# ArdZeroBTHIDStickBckUp.net
KiCad netlist of a schematic drawn in EAGLE
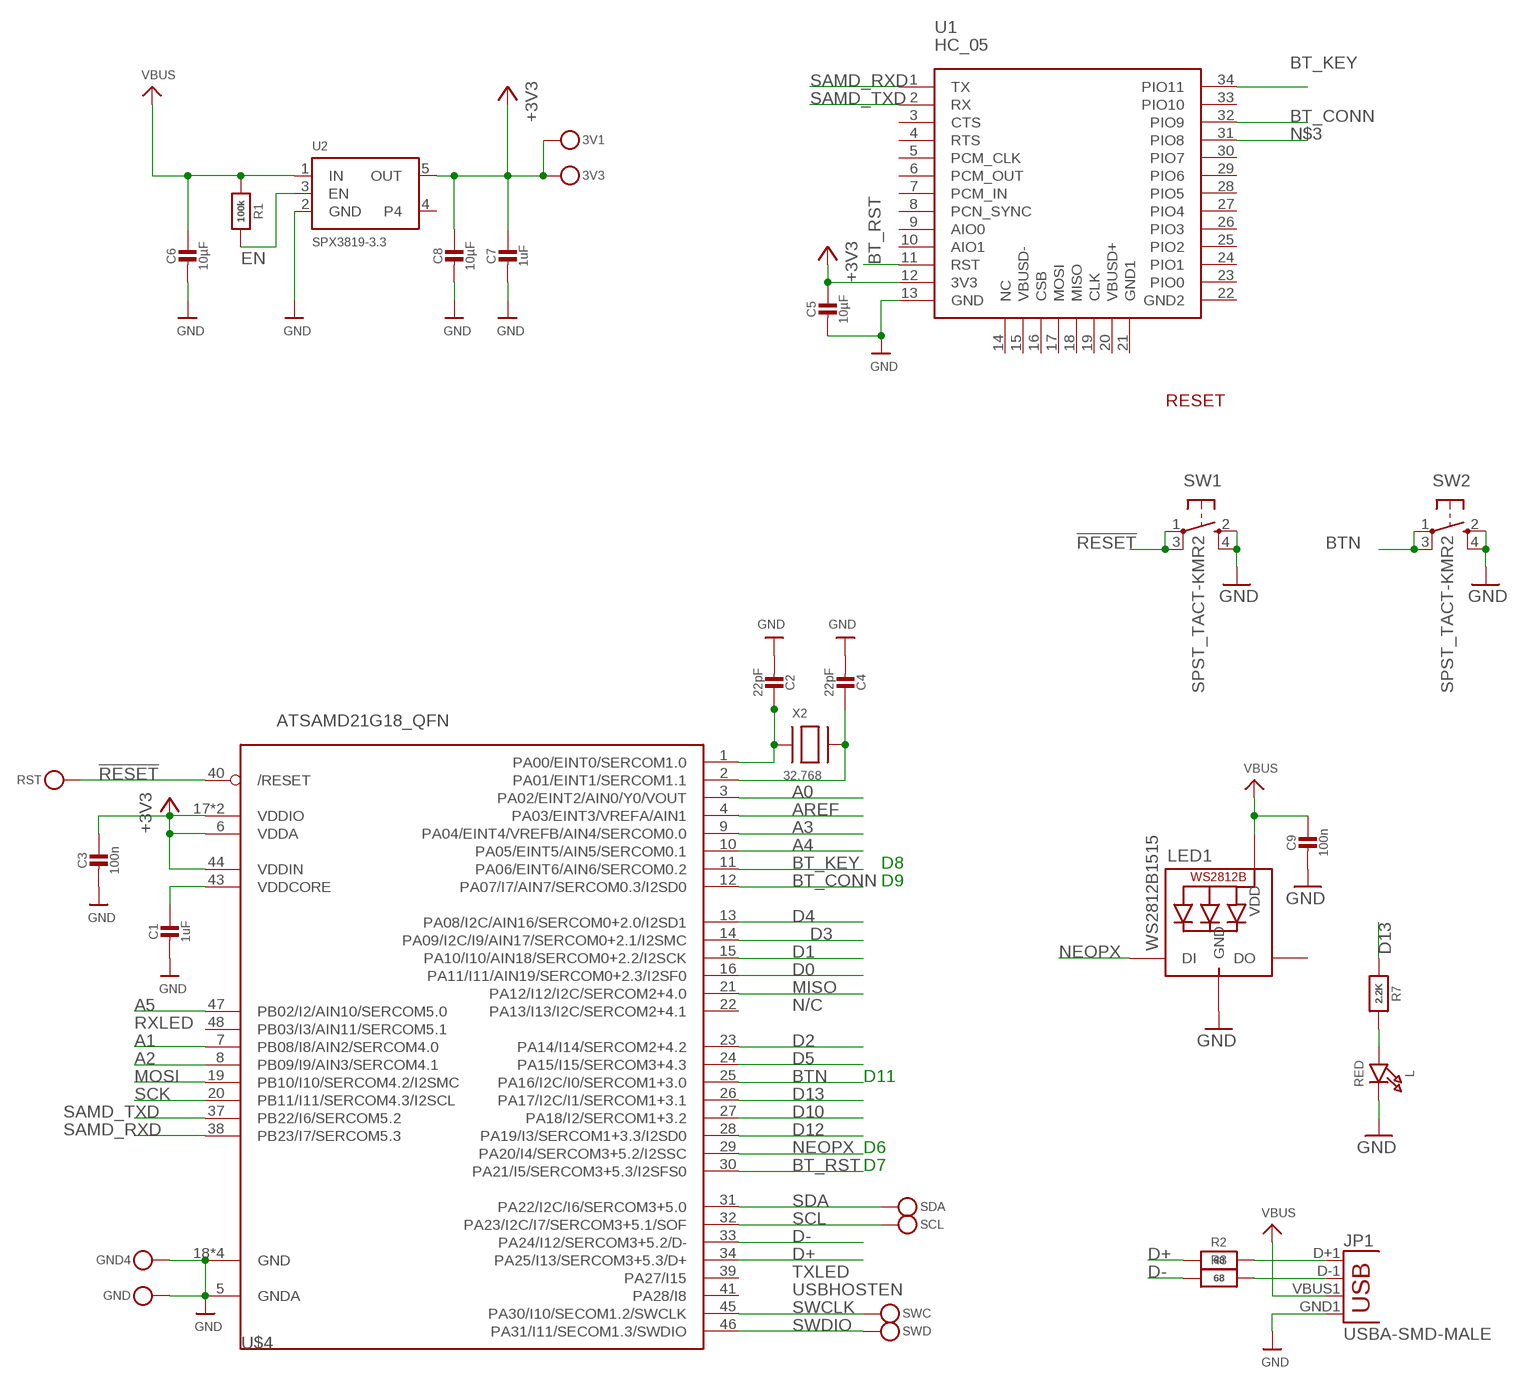
[diagram p0: schematic, sheet 1]

(export (version "E")
  (design (tool "Eeschema 10.0.6"))
  (components
    (comp (ref "3V1")
      (value "TESTPOINTROUND1.5MM")
      (footprint "eagle-import:TESTPOINT_ROUND_1.5MM")
      (libsource (lib "eagle-import") (part "TESTPOINTROUND1.5MM"))
    )
    (comp (ref "3V3")
      (value "TESTPOINTROUND1.5MM")
      (footprint "eagle-import:TESTPOINT_ROUND_1.5MM")
      (libsource (lib "eagle-import") (part "TESTPOINTROUND1.5MM"))
    )
    (comp (ref "C1")
      (value "1uF")
      (footprint "eagle-import:0603-NO")
      (libsource (lib "eagle-import") (part "CAP_CERAMIC0603_NO"))
    )
    (comp (ref "C2")
      (value "22pF")
      (footprint "eagle-import:0603-NO")
      (libsource (lib "eagle-import") (part "CAP_CERAMIC0603_NO"))
    )
    (comp (ref "C3")
      (value "100n")
      (footprint "eagle-import:0603-NO")
      (libsource (lib "eagle-import") (part "CAP_CERAMIC0603_NO"))
    )
    (comp (ref "C4")
      (value "22pF")
      (footprint "eagle-import:0603-NO")
      (libsource (lib "eagle-import") (part "CAP_CERAMIC0603_NO"))
    )
    (comp (ref "C5")
      (value "10µF")
      (footprint "eagle-import:0805-NO")
      (libsource (lib "eagle-import") (part "CAP_CERAMIC0805-NOOUTLINE"))
    )
    (comp (ref "C6")
      (value "10µF")
      (footprint "eagle-import:0805-NO")
      (libsource (lib "eagle-import") (part "CAP_CERAMIC0805-NOOUTLINE"))
    )
    (comp (ref "C7")
      (value "1uF")
      (footprint "eagle-import:0603-NO")
      (libsource (lib "eagle-import") (part "CAP_CERAMIC0603_NO"))
    )
    (comp (ref "C8")
      (value "10µF")
      (footprint "eagle-import:0805-NO")
      (libsource (lib "eagle-import") (part "CAP_CERAMIC0805-NOOUTLINE"))
    )
    (comp (ref "C9")
      (value "100n")
      (footprint "eagle-import:0603-NO")
      (libsource (lib "eagle-import") (part "CAP_CERAMIC0603_NO"))
    )
    (comp (ref "GND")
      (value "TESTPOINTROUND1.5MM")
      (footprint "eagle-import:TESTPOINT_ROUND_1.5MM")
      (libsource (lib "eagle-import") (part "TESTPOINTROUND1.5MM"))
    )
    (comp (ref "GND4")
      (value "TESTPOINTROUND1.5MM")
      (footprint "eagle-import:TESTPOINT_ROUND_1.5MM")
      (libsource (lib "eagle-import") (part "TESTPOINTROUND1.5MM"))
    )
    (comp (ref "JP1")
      (value "USBA-SMD-MALE")
      (footprint "eagle-import:USB-A-SMT-MALE")
      (libsource (lib "eagle-import") (part "USBA-SMD-MALE"))
    )
    (comp (ref "L")
      (value "RED")
      (footprint "eagle-import:CHIPLED_0805_NOOUTLINE")
      (libsource (lib "eagle-import") (part "LED0805_NOOUTLINE"))
    )
    (comp (ref "LED1")
      (value "WS2812B1515")
      (footprint "eagle-import:LED1515")
      (libsource (lib "eagle-import") (part "WS2812B1515"))
    )
    (comp (ref "R1")
      (value "100k")
      (footprint "eagle-import:0603-NO")
      (libsource (lib "eagle-import") (part "RESISTOR_0603_NOOUT"))
    )
    (comp (ref "R2")
      (value "68")
      (footprint "eagle-import:0603-NO")
      (libsource (lib "eagle-import") (part "RESISTOR_0603_NOOUT"))
    )
    (comp (ref "R3")
      (value "68")
      (footprint "eagle-import:0603-NO")
      (libsource (lib "eagle-import") (part "RESISTOR_0603_NOOUT"))
    )
    (comp (ref "R7")
      (value "2.2K")
      (footprint "eagle-import:0603-NO")
      (libsource (lib "eagle-import") (part "RESISTOR_0603_NOOUT"))
    )
    (comp (ref "RST")
      (value "TESTPOINTROUND1.5MM")
      (footprint "eagle-import:TESTPOINT_ROUND_1.5MM")
      (libsource (lib "eagle-import") (part "TESTPOINTROUND1.5MM"))
    )
    (comp (ref "SCL")
      (value "TESTPOINTROUND1.5MM")
      (footprint "eagle-import:TESTPOINT_ROUND_1.5MM")
      (libsource (lib "eagle-import") (part "TESTPOINTROUND1.5MM"))
    )
    (comp (ref "SDA")
      (value "TESTPOINTROUND1.5MM")
      (footprint "eagle-import:TESTPOINT_ROUND_1.5MM")
      (libsource (lib "eagle-import") (part "TESTPOINTROUND1.5MM"))
    )
    (comp (ref "SW1")
      (value "SPST_TACT-KMR2")
      (footprint "eagle-import:KMR2")
      (libsource (lib "eagle-import") (part "SPST_TACT-KMR2"))
    )
    (comp (ref "SW2")
      (value "SPST_TACT-KMR2")
      (footprint "eagle-import:KMR2")
      (libsource (lib "eagle-import") (part "SPST_TACT-KMR2"))
    )
    (comp (ref "SWC")
      (value "TESTPOINTROUND1.5MM")
      (footprint "eagle-import:TESTPOINT_ROUND_1.5MM")
      (libsource (lib "eagle-import") (part "TESTPOINTROUND1.5MM"))
    )
    (comp (ref "SWD")
      (value "TESTPOINTROUND1.5MM")
      (footprint "eagle-import:TESTPOINT_ROUND_1.5MM")
      (libsource (lib "eagle-import") (part "TESTPOINTROUND1.5MM"))
    )
    (comp (ref "U$4")
      (value "ATSAMD21G18_QFN")
      (footprint "eagle-import:TQFN48_7MM")
      (libsource (lib "eagle-import") (part "ATSAMD21J_QFN"))
    )
    (comp (ref "U1")
      (value "HC_05")
      (footprint "eagle-import:BLUETOOTH_SMD")
      (libsource (lib "eagle-import") (part "HC_05"))
    )
    (comp (ref "U2")
      (value "SPX3819-3.3")
      (footprint "eagle-import:SOT23-5")
      (libsource (lib "eagle-import") (part "VREG_SOT23-5"))
    )
    (comp (ref "X2")
      (value "32.768")
      (footprint "eagle-import:XTAL3215")
      (libsource (lib "eagle-import") (part "XTAL-3.2X1.5"))
    )
  )
  (nets
    (net (code "1") (name "+3V3") (class "Default")
      (node (ref "3V1") (pin "P$1") (pinfunction "P$1_P$1") (pintype "bidirectional"))
      (node (ref "3V3") (pin "P$1") (pinfunction "P$1_P$1") (pintype "bidirectional"))
      (node (ref "C3") (pin "1") (pinfunction "1_1") (pintype "passive"))
      (node (ref "C5") (pin "1") (pinfunction "1_1") (pintype "passive"))
      (node (ref "C7") (pin "1") (pinfunction "1_1") (pintype "passive"))
      (node (ref "C8") (pin "1") (pinfunction "1_1") (pintype "passive"))
      (node (ref "U$4") (pin "17") (pinfunction "VDDIO_17") (pintype "power_in"))
      (node (ref "U$4") (pin "36") (pinfunction "VDDIO_36") (pintype "power_in"))
      (node (ref "U$4") (pin "44") (pinfunction "VDDIN_44") (pintype "power_in"))
      (node (ref "U$4") (pin "6") (pinfunction "VDDA_6") (pintype "power_in"))
      (node (ref "U1") (pin "12") (pinfunction "3V3_12") (pintype "bidirectional"))
      (node (ref "U2") (pin "5") (pinfunction "OUT_5") (pintype "power_in"))
    )
    (net (code "2") (name "/A0") (class "Default")
      (node (ref "U$4") (pin "3") (pinfunction "PA02/EINT2/AIN0/Y0/VOUT_3") (pintype "bidirectional"))
    )
    (net (code "3") (name "/A1") (class "Default")
      (node (ref "U$4") (pin "7") (pinfunction "PB08/I8/AIN2/SERCOM4.0_7") (pintype "bidirectional"))
    )
    (net (code "4") (name "/A2") (class "Default")
      (node (ref "U$4") (pin "8") (pinfunction "PB09/I9/AIN3/SERCOM4.1_8") (pintype "bidirectional"))
    )
    (net (code "5") (name "/A3") (class "Default")
      (node (ref "U$4") (pin "9") (pinfunction "PA04/EINT4/VREFB/AIN4/SERCOM0.0_9") (pintype "bidirectional"))
    )
    (net (code "6") (name "/A4") (class "Default")
      (node (ref "U$4") (pin "10") (pinfunction "PA05/EINT5/AIN5/SERCOM0.1_10") (pintype "bidirectional"))
    )
    (net (code "7") (name "/A5") (class "Default")
      (node (ref "U$4") (pin "47") (pinfunction "PB02/I2/AIN10/SERCOM5.0_47") (pintype "bidirectional"))
    )
    (net (code "8") (name "/AREF") (class "Default")
      (node (ref "U$4") (pin "4") (pinfunction "PA03/EINT3/VREFA/AIN1_4") (pintype "bidirectional"))
    )
    (net (code "9") (name "/BTN") (class "Default")
      (node (ref "SW2") (pin "1") (pinfunction "P_1") (pintype "passive"))
      (node (ref "SW2") (pin "3") (pinfunction "P1_3") (pintype "passive"))
      (node (ref "U$4") (pin "25") (pinfunction "PA16/I2C/I0/SERCOM1+3.0_25") (pintype "bidirectional"))
    )
    (net (code "10") (name "/BT_CONN") (class "Default")
      (node (ref "U$4") (pin "12") (pinfunction "PA07/I7/AIN7/SERCOM0.3/I2SD0_12") (pintype "bidirectional"))
      (node (ref "U1") (pin "32") (pinfunction "PIO9_32") (pintype "bidirectional"))
    )
    (net (code "11") (name "/BT_KEY") (class "Default")
      (node (ref "U$4") (pin "11") (pinfunction "PA06/EINT6/AIN6/SERCOM0.2_11") (pintype "bidirectional"))
      (node (ref "U1") (pin "34") (pinfunction "PIO11_34") (pintype "bidirectional"))
    )
    (net (code "12") (name "/BT_RST") (class "Default")
      (node (ref "U$4") (pin "30") (pinfunction "PA21/I5/SERCOM3+5.3/I2SFS0_30") (pintype "bidirectional"))
      (node (ref "U1") (pin "11") (pinfunction "RST_11") (pintype "bidirectional"))
    )
    (net (code "13") (name "/D+") (class "Default")
      (node (ref "R2") (pin "1") (pinfunction "1_1") (pintype "passive"))
      (node (ref "U$4") (pin "34") (pinfunction "PA25/I13/SERCOM3+5.3/D+_34") (pintype "bidirectional"))
    )
    (net (code "14") (name "/D-") (class "Default")
      (node (ref "R3") (pin "1") (pinfunction "1_1") (pintype "passive"))
      (node (ref "U$4") (pin "33") (pinfunction "PA24/I12/SERCOM3+5.2/D-_33") (pintype "bidirectional"))
    )
    (net (code "15") (name "/D0") (class "Default")
      (node (ref "U$4") (pin "16") (pinfunction "PA11/I11/AIN19/SERCOM0+2.3/I2SF0_16") (pintype "bidirectional"))
    )
    (net (code "16") (name "/D1") (class "Default")
      (node (ref "U$4") (pin "15") (pinfunction "PA10/I10/AIN18/SERCOM0+2.2/I2SCK_15") (pintype "bidirectional"))
    )
    (net (code "17") (name "/D2") (class "Default")
      (node (ref "U$4") (pin "23") (pinfunction "PA14/I14/SERCOM2+4.2_23") (pintype "bidirectional"))
    )
    (net (code "18") (name "/D3") (class "Default")
      (node (ref "U$4") (pin "14") (pinfunction "PA09/I2C/I9/AIN17/SERCOM0+2.1/I2SMC_14") (pintype "bidirectional"))
    )
    (net (code "19") (name "/D4") (class "Default")
      (node (ref "U$4") (pin "13") (pinfunction "PA08/I2C/AIN16/SERCOM0+2.0/I2SD1_13") (pintype "bidirectional"))
    )
    (net (code "20") (name "/D5") (class "Default")
      (node (ref "U$4") (pin "24") (pinfunction "PA15/I15/SERCOM3+4.3_24") (pintype "bidirectional"))
    )
    (net (code "21") (name "/D10") (class "Default")
      (node (ref "U$4") (pin "27") (pinfunction "PA18/I2/SERCOM1+3.2_27") (pintype "bidirectional"))
    )
    (net (code "22") (name "/D12") (class "Default")
      (node (ref "U$4") (pin "28") (pinfunction "PA19/I3/SERCOM1+3.3/I2SD0_28") (pintype "bidirectional"))
    )
    (net (code "23") (name "/D13") (class "Default")
      (node (ref "R7") (pin "1") (pinfunction "1_1") (pintype "passive"))
      (node (ref "U$4") (pin "26") (pinfunction "PA17/I2C/I1/SERCOM1+3.1_26") (pintype "bidirectional"))
    )
    (net (code "24") (name "/EN") (class "Default")
      (node (ref "R1") (pin "2") (pinfunction "2_2") (pintype "passive"))
      (node (ref "U2") (pin "3") (pinfunction "EN_3") (pintype "input"))
    )
    (net (code "25") (name "/MISO") (class "Default")
      (node (ref "U$4") (pin "21") (pinfunction "PA12/I12/I2C/SERCOM2+4.0_21") (pintype "bidirectional"))
    )
    (net (code "26") (name "/MOSI") (class "Default")
      (node (ref "U$4") (pin "19") (pinfunction "PB10/I10/SERCOM4.2/I2SMC_19") (pintype "bidirectional"))
    )
    (net (code "27") (name "/N$3") (class "Default")
      (node (ref "U1") (pin "31") (pinfunction "PIO8_31") (pintype "bidirectional"))
    )
    (net (code "28") (name "/NEOPX") (class "Default")
      (node (ref "LED1") (pin "DIN") (pinfunction "DI_DIN") (pintype "input"))
      (node (ref "U$4") (pin "29") (pinfunction "PA20/I4/SERCOM3+5.2/I2SSC_29") (pintype "bidirectional"))
    )
    (net (code "29") (name "/SAMD_RXD") (class "Default")
      (node (ref "U$4") (pin "38") (pinfunction "PB23/I7/SERCOM5.3_38") (pintype "bidirectional"))
      (node (ref "U1") (pin "1") (pinfunction "TX_1") (pintype "bidirectional"))
    )
    (net (code "30") (name "/SAMD_TXD") (class "Default")
      (node (ref "U$4") (pin "37") (pinfunction "PB22/I6/SERCOM5.2_37") (pintype "bidirectional"))
      (node (ref "U1") (pin "2") (pinfunction "RX_2") (pintype "bidirectional"))
    )
    (net (code "31") (name "/SCK") (class "Default")
      (node (ref "U$4") (pin "20") (pinfunction "PB11/I11/SERCOM4.3/I2SCL_20") (pintype "bidirectional"))
    )
    (net (code "32") (name "/SCL") (class "Default")
      (node (ref "SCL") (pin "P$1") (pinfunction "P$1_P$1") (pintype "bidirectional"))
      (node (ref "U$4") (pin "32") (pinfunction "PA23/I2C/I7/SERCOM3+5.1/SOF_32") (pintype "bidirectional"))
    )
    (net (code "33") (name "/SDA") (class "Default")
      (node (ref "SDA") (pin "P$1") (pinfunction "P$1_P$1") (pintype "bidirectional"))
      (node (ref "U$4") (pin "31") (pinfunction "PA22/I2C/I6/SERCOM3+5.0_31") (pintype "bidirectional"))
    )
    (net (code "34") (name "/SWCLK") (class "Default")
      (node (ref "SWC") (pin "P$1") (pinfunction "P$1_P$1") (pintype "bidirectional"))
      (node (ref "U$4") (pin "45") (pinfunction "PA30/I10/SECOM1.2/SWCLK_45") (pintype "bidirectional"))
    )
    (net (code "35") (name "/SWDIO") (class "Default")
      (node (ref "SWD") (pin "P$1") (pinfunction "P$1_P$1") (pintype "bidirectional"))
      (node (ref "U$4") (pin "46") (pinfunction "PA31/I11/SECOM1.3/SWDIO_46") (pintype "bidirectional"))
    )
    (net (code "36") (name "/~{RESET}") (class "Default")
      (node (ref "RST") (pin "P$1") (pinfunction "P$1_P$1") (pintype "bidirectional"))
      (node (ref "SW1") (pin "1") (pinfunction "P_1") (pintype "passive"))
      (node (ref "SW1") (pin "3") (pinfunction "P1_3") (pintype "passive"))
      (node (ref "U$4") (pin "40") (pinfunction "/RESET_40") (pintype "bidirectional"))
    )
    (net (code "37") (name "GND") (class "Default")
      (node (ref "C1") (pin "2") (pinfunction "2_2") (pintype "passive"))
      (node (ref "C2") (pin "2") (pinfunction "2_2") (pintype "passive"))
      (node (ref "C3") (pin "2") (pinfunction "2_2") (pintype "passive"))
      (node (ref "C4") (pin "2") (pinfunction "2_2") (pintype "passive"))
      (node (ref "C5") (pin "2") (pinfunction "2_2") (pintype "passive"))
      (node (ref "C6") (pin "2") (pinfunction "2_2") (pintype "passive"))
      (node (ref "C7") (pin "2") (pinfunction "2_2") (pintype "passive"))
      (node (ref "C8") (pin "2") (pinfunction "2_2") (pintype "passive"))
      (node (ref "C9") (pin "2") (pinfunction "2_2") (pintype "passive"))
      (node (ref "GND") (pin "P$1") (pinfunction "P$1_P$1") (pintype "bidirectional"))
      (node (ref "GND4") (pin "P$1") (pinfunction "P$1_P$1") (pintype "bidirectional"))
      (node (ref "JP1") (pin "GND1") (pinfunction "GND_GND1") (pintype "bidirectional"))
      (node (ref "L") (pin "C") (pinfunction "C_C") (pintype "passive"))
      (node (ref "LED1") (pin "GND") (pinfunction "GND_GND") (pintype "power_in"))
      (node (ref "SW1") (pin "2") (pinfunction "S_2") (pintype "passive"))
      (node (ref "SW1") (pin "4") (pinfunction "S1_4") (pintype "passive"))
      (node (ref "SW2") (pin "2") (pinfunction "S_2") (pintype "passive"))
      (node (ref "SW2") (pin "4") (pinfunction "S1_4") (pintype "passive"))
      (node (ref "U$4") (pin "18") (pinfunction "GND_18") (pintype "power_in"))
      (node (ref "U$4") (pin "35") (pinfunction "GND_35") (pintype "power_in"))
      (node (ref "U$4") (pin "42") (pinfunction "GND_42") (pintype "power_in"))
      (node (ref "U$4") (pin "5") (pinfunction "GNDA_5") (pintype "power_in"))
      (node (ref "U$4") (pin "THERMAL") (pinfunction "GND_THERMAL") (pintype "power_in"))
      (node (ref "U1") (pin "13") (pinfunction "GND_13") (pintype "bidirectional"))
      (node (ref "U2") (pin "2") (pinfunction "GND_2") (pintype "power_in"))
    )
    (net (code "38") (name "Net-(JP1-D+)") (class "Default")
      (node (ref "JP1") (pin "D+1") (pinfunction "D+_D+1") (pintype "bidirectional"))
      (node (ref "R2") (pin "2") (pinfunction "2_2") (pintype "passive"))
    )
    (net (code "39") (name "Net-(JP1-D-)") (class "Default")
      (node (ref "JP1") (pin "D-1") (pinfunction "D-_D-1") (pintype "bidirectional"))
      (node (ref "R3") (pin "2") (pinfunction "2_2") (pintype "passive"))
    )
    (net (code "40") (name "Net-(L-PadA)") (class "Default")
      (node (ref "L") (pin "A") (pinfunction "A_A") (pintype "passive"))
      (node (ref "R7") (pin "2") (pinfunction "2_2") (pintype "passive"))
    )
    (net (code "41") (name "Net-(U$4-PA00{slash}EINT0{slash}SERCOM1.0)") (class "Default")
      (node (ref "C2") (pin "1") (pinfunction "1_1") (pintype "passive"))
      (node (ref "U$4") (pin "1") (pinfunction "PA00/EINT0/SERCOM1.0_1") (pintype "bidirectional"))
      (node (ref "X2") (pin "P$1") (pinfunction "P$1_P$1") (pintype "bidirectional"))
    )
    (net (code "42") (name "Net-(U$4-PA01{slash}EINT1{slash}SERCOM1.1)") (class "Default")
      (node (ref "C4") (pin "1") (pinfunction "1_1") (pintype "passive"))
      (node (ref "U$4") (pin "2") (pinfunction "PA01/EINT1/SERCOM1.1_2") (pintype "bidirectional"))
      (node (ref "X2") (pin "P$2") (pinfunction "P$2_P$2") (pintype "bidirectional"))
    )
    (net (code "43") (name "Net-(U$4-VDDCORE)") (class "Default")
      (node (ref "C1") (pin "1") (pinfunction "1_1") (pintype "passive"))
      (node (ref "U$4") (pin "43") (pinfunction "VDDCORE_43") (pintype "power_in"))
    )
    (net (code "44") (name "VBUS") (class "Default")
      (node (ref "C6") (pin "1") (pinfunction "1_1") (pintype "passive"))
      (node (ref "C9") (pin "1") (pinfunction "1_1") (pintype "passive"))
      (node (ref "JP1") (pin "VBUS1") (pinfunction "VBUS_VBUS1") (pintype "bidirectional"))
      (node (ref "LED1") (pin "VDD") (pinfunction "VDD_VDD") (pintype "power_in"))
      (node (ref "R1") (pin "1") (pinfunction "1_1") (pintype "passive"))
      (node (ref "U2") (pin "1") (pinfunction "IN_1") (pintype "power_in"))
    )
    (net (code "45") (name "unconnected-(LED1-DO-PadDOUT)") (class "Default")
      (node (ref "LED1") (pin "DOUT") (pinfunction "DO_DOUT") (pintype "output"))
    )
    (net (code "46") (name "unconnected-(U$4-PA13{slash}I13{slash}I2C{slash}SERCOM2+4.1-Pad22)") (class "Default")
      (node (ref "U$4") (pin "22") (pinfunction "PA13/I13/I2C/SERCOM2+4.1_22") (pintype "bidirectional"))
    )
    (net (code "47") (name "unconnected-(U$4-PA27{slash}I15-Pad39)") (class "Default")
      (node (ref "U$4") (pin "39") (pinfunction "PA27/I15_39") (pintype "bidirectional"))
    )
    (net (code "48") (name "unconnected-(U$4-PA28{slash}I8-Pad41)") (class "Default")
      (node (ref "U$4") (pin "41") (pinfunction "PA28/I8_41") (pintype "bidirectional"))
    )
    (net (code "49") (name "unconnected-(U$4-PB03{slash}I3{slash}AIN11{slash}SERCOM5.1-Pad48)") (class "Default")
      (node (ref "U$4") (pin "48") (pinfunction "PB03/I3/AIN11/SERCOM5.1_48") (pintype "bidirectional"))
    )
    (net (code "50") (name "unconnected-(U1-AIO0-Pad9)") (class "Default")
      (node (ref "U1") (pin "9") (pinfunction "AIO0_9") (pintype "bidirectional"))
    )
    (net (code "51") (name "unconnected-(U1-AIO1-Pad10)") (class "Default")
      (node (ref "U1") (pin "10") (pinfunction "AIO1_10") (pintype "bidirectional"))
    )
    (net (code "52") (name "unconnected-(U1-CLK-Pad19)") (class "Default")
      (node (ref "U1") (pin "19") (pinfunction "CLK_19") (pintype "bidirectional"))
    )
    (net (code "53") (name "unconnected-(U1-CSB-Pad16)") (class "Default")
      (node (ref "U1") (pin "16") (pinfunction "CSB_16") (pintype "bidirectional"))
    )
    (net (code "54") (name "unconnected-(U1-CTS-Pad3)") (class "Default")
      (node (ref "U1") (pin "3") (pinfunction "CTS_3") (pintype "bidirectional"))
    )
    (net (code "55") (name "unconnected-(U1-GND1-Pad21)") (class "Default")
      (node (ref "U1") (pin "21") (pinfunction "GND1_21") (pintype "bidirectional"))
    )
    (net (code "56") (name "unconnected-(U1-GND2-Pad22)") (class "Default")
      (node (ref "U1") (pin "22") (pinfunction "GND2_22") (pintype "bidirectional"))
    )
    (net (code "57") (name "unconnected-(U1-MISO-Pad18)") (class "Default")
      (node (ref "U1") (pin "18") (pinfunction "MISO_18") (pintype "bidirectional"))
    )
    (net (code "58") (name "unconnected-(U1-MOSI-Pad17)") (class "Default")
      (node (ref "U1") (pin "17") (pinfunction "MOSI_17") (pintype "bidirectional"))
    )
    (net (code "59") (name "unconnected-(U1-NC-Pad14)") (class "Default")
      (node (ref "U1") (pin "14") (pinfunction "NC_14") (pintype "bidirectional"))
    )
    (net (code "60") (name "unconnected-(U1-PCM_CLK-Pad5)") (class "Default")
      (node (ref "U1") (pin "5") (pinfunction "PCM_CLK_5") (pintype "bidirectional"))
    )
    (net (code "61") (name "unconnected-(U1-PCM_IN-Pad7)") (class "Default")
      (node (ref "U1") (pin "7") (pinfunction "PCM_IN_7") (pintype "bidirectional"))
    )
    (net (code "62") (name "unconnected-(U1-PCM_OUT-Pad6)") (class "Default")
      (node (ref "U1") (pin "6") (pinfunction "PCM_OUT_6") (pintype "bidirectional"))
    )
    (net (code "63") (name "unconnected-(U1-PCN_SYNC-Pad8)") (class "Default")
      (node (ref "U1") (pin "8") (pinfunction "PCN_SYNC_8") (pintype "bidirectional"))
    )
    (net (code "64") (name "unconnected-(U1-PIO0-Pad23)") (class "Default")
      (node (ref "U1") (pin "23") (pinfunction "PIO0_23") (pintype "bidirectional"))
    )
    (net (code "65") (name "unconnected-(U1-PIO1-Pad24)") (class "Default")
      (node (ref "U1") (pin "24") (pinfunction "PIO1_24") (pintype "bidirectional"))
    )
    (net (code "66") (name "unconnected-(U1-PIO2-Pad25)") (class "Default")
      (node (ref "U1") (pin "25") (pinfunction "PIO2_25") (pintype "bidirectional"))
    )
    (net (code "67") (name "unconnected-(U1-PIO3-Pad26)") (class "Default")
      (node (ref "U1") (pin "26") (pinfunction "PIO3_26") (pintype "bidirectional"))
    )
    (net (code "68") (name "unconnected-(U1-PIO4-Pad27)") (class "Default")
      (node (ref "U1") (pin "27") (pinfunction "PIO4_27") (pintype "bidirectional"))
    )
    (net (code "69") (name "unconnected-(U1-PIO5-Pad28)") (class "Default")
      (node (ref "U1") (pin "28") (pinfunction "PIO5_28") (pintype "bidirectional"))
    )
    (net (code "70") (name "unconnected-(U1-PIO6-Pad29)") (class "Default")
      (node (ref "U1") (pin "29") (pinfunction "PIO6_29") (pintype "bidirectional"))
    )
    (net (code "71") (name "unconnected-(U1-PIO7-Pad30)") (class "Default")
      (node (ref "U1") (pin "30") (pinfunction "PIO7_30") (pintype "bidirectional"))
    )
    (net (code "72") (name "unconnected-(U1-PIO10-Pad33)") (class "Default")
      (node (ref "U1") (pin "33") (pinfunction "PIO10_33") (pintype "bidirectional"))
    )
    (net (code "73") (name "unconnected-(U1-RTS-Pad4)") (class "Default")
      (node (ref "U1") (pin "4") (pinfunction "RTS_4") (pintype "bidirectional"))
    )
    (net (code "74") (name "unconnected-(U1-VBUSD+-Pad20)") (class "Default")
      (node (ref "U1") (pin "20") (pinfunction "VBUSD+_20") (pintype "bidirectional"))
    )
    (net (code "75") (name "unconnected-(U1-VBUSD--Pad15)") (class "Default")
      (node (ref "U1") (pin "15") (pinfunction "VBUSD-_15") (pintype "bidirectional"))
    )
    (net (code "76") (name "unconnected-(U2-P4-Pad4)") (class "Default")
      (node (ref "U2") (pin "4") (pinfunction "P4_4") (pintype "bidirectional"))
    )
  )
)
